# Exp_Board_Slolu.net
KiCad netlist of a schematic drawn in EAGLE
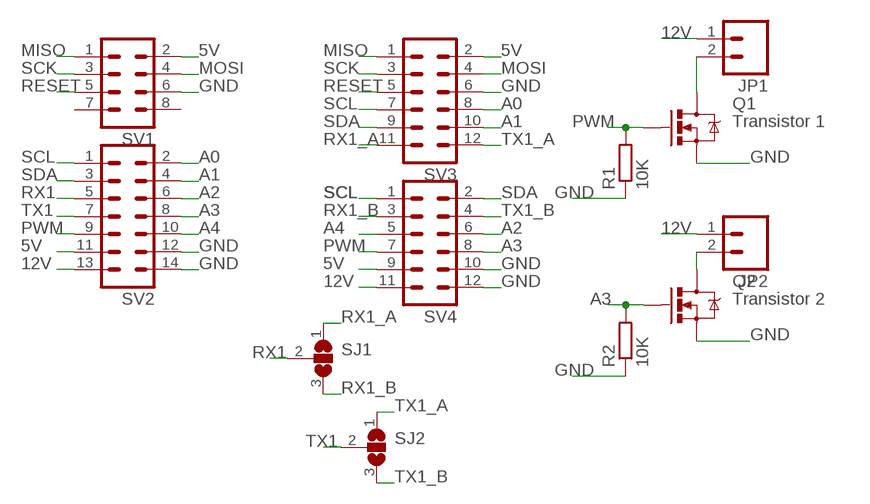
[diagram p0: schematic, sheet 1]

(export (version "E")
  (design (tool "Eeschema 10.0.6"))
  (components
    (comp (ref "JP1")
      (value "M02PTH")
      (footprint "eagle-import:1X02")
      (libsource (lib "eagle-import") (part "M02PTH"))
    )
    (comp (ref "JP2")
      (value "M02PTH")
      (footprint "eagle-import:1X02")
      (libsource (lib "eagle-import") (part "M02PTH"))
    )
    (comp (ref "Q1")
      (value "Transistor 1")
      (footprint "eagle-import:TO220V")
      (libsource (lib "eagle-import") (part "MOSFET-NCHANNELPTH2"))
    )
    (comp (ref "Q2")
      (value "Transistor 2")
      (footprint "eagle-import:TO220V")
      (libsource (lib "eagle-import") (part "MOSFET-NCHANNELPTH2"))
    )
    (comp (ref "R1")
      (value "10K")
      (footprint "eagle-import:0204_7")
      (libsource (lib "eagle-import") (part "R-EU_0204/7"))
    )
    (comp (ref "R2")
      (value "10K")
      (footprint "eagle-import:0204_7")
      (libsource (lib "eagle-import") (part "R-EU_0204/7"))
    )
    (comp (ref "SJ1")
      (value "SJ2W")
      (footprint "eagle-import:SJ_2")
      (libsource (lib "eagle-import") (part "SJ2W"))
    )
    (comp (ref "SJ2")
      (value "SJ2W")
      (footprint "eagle-import:SJ_2")
      (libsource (lib "eagle-import") (part "SJ2W"))
    )
    (comp (ref "SV1")
      (value "MA04-2")
      (footprint "eagle-import:MA04-2")
      (libsource (lib "eagle-import") (part "MA04-2"))
    )
    (comp (ref "SV2")
      (value "MA07-2")
      (footprint "eagle-import:MA07-2")
      (libsource (lib "eagle-import") (part "MA07-2"))
    )
    (comp (ref "SV3")
      (value "MA06-2")
      (footprint "eagle-import:MA06-2")
      (libsource (lib "eagle-import") (part "MA06-2"))
    )
    (comp (ref "SV4")
      (value "MA06-2")
      (footprint "eagle-import:MA06-2")
      (libsource (lib "eagle-import") (part "MA06-2"))
    )
  )
  (nets
    (net (code "1") (name "/5V") (class "Default")
      (node (ref "SV1") (pin "2") (pinfunction "2_2") (pintype "passive"))
      (node (ref "SV2") (pin "11") (pinfunction "11_11") (pintype "passive"))
      (node (ref "SV3") (pin "2") (pinfunction "2_2") (pintype "passive"))
      (node (ref "SV4") (pin "9") (pinfunction "9_9") (pintype "passive"))
    )
    (net (code "2") (name "/12V") (class "Default")
      (node (ref "JP1") (pin "1") (pinfunction "1_1") (pintype "passive"))
      (node (ref "JP2") (pin "1") (pinfunction "1_1") (pintype "passive"))
      (node (ref "SV2") (pin "13") (pinfunction "13_13") (pintype "passive"))
      (node (ref "SV4") (pin "11") (pinfunction "11_11") (pintype "passive"))
    )
    (net (code "3") (name "/A0") (class "Default")
      (node (ref "SV2") (pin "2") (pinfunction "2_2") (pintype "passive"))
      (node (ref "SV3") (pin "8") (pinfunction "8_8") (pintype "passive"))
    )
    (net (code "4") (name "/A1") (class "Default")
      (node (ref "SV2") (pin "4") (pinfunction "4_4") (pintype "passive"))
      (node (ref "SV3") (pin "10") (pinfunction "10_10") (pintype "passive"))
    )
    (net (code "5") (name "/A2") (class "Default")
      (node (ref "SV2") (pin "6") (pinfunction "6_6") (pintype "passive"))
      (node (ref "SV4") (pin "6") (pinfunction "6_6") (pintype "passive"))
    )
    (net (code "6") (name "/A3") (class "Default")
      (node (ref "Q2") (pin "1") (pinfunction "G_1") (pintype "passive"))
      (node (ref "R2") (pin "2") (pinfunction "2_2") (pintype "passive"))
      (node (ref "SV2") (pin "8") (pinfunction "8_8") (pintype "passive"))
      (node (ref "SV4") (pin "8") (pinfunction "8_8") (pintype "passive"))
    )
    (net (code "7") (name "/A4") (class "Default")
      (node (ref "SV2") (pin "10") (pinfunction "10_10") (pintype "passive"))
      (node (ref "SV4") (pin "5") (pinfunction "5_5") (pintype "passive"))
    )
    (net (code "8") (name "/GND") (class "Default")
      (node (ref "Q1") (pin "3") (pinfunction "S_3") (pintype "passive"))
      (node (ref "Q2") (pin "3") (pinfunction "S_3") (pintype "passive"))
      (node (ref "R1") (pin "1") (pinfunction "1_1") (pintype "passive"))
      (node (ref "R2") (pin "1") (pinfunction "1_1") (pintype "passive"))
      (node (ref "SV1") (pin "6") (pinfunction "6_6") (pintype "passive"))
      (node (ref "SV2") (pin "12") (pinfunction "12_12") (pintype "passive"))
      (node (ref "SV2") (pin "14") (pinfunction "14_14") (pintype "passive"))
      (node (ref "SV3") (pin "6") (pinfunction "6_6") (pintype "passive"))
      (node (ref "SV4") (pin "10") (pinfunction "10_10") (pintype "passive"))
      (node (ref "SV4") (pin "12") (pinfunction "12_12") (pintype "passive"))
    )
    (net (code "9") (name "/MISO") (class "Default")
      (node (ref "SV1") (pin "1") (pinfunction "1_1") (pintype "passive"))
      (node (ref "SV3") (pin "1") (pinfunction "1_1") (pintype "passive"))
    )
    (net (code "10") (name "/MOSI") (class "Default")
      (node (ref "SV1") (pin "4") (pinfunction "4_4") (pintype "passive"))
      (node (ref "SV3") (pin "4") (pinfunction "4_4") (pintype "passive"))
    )
    (net (code "11") (name "/PWM") (class "Default")
      (node (ref "Q1") (pin "1") (pinfunction "G_1") (pintype "passive"))
      (node (ref "R1") (pin "2") (pinfunction "2_2") (pintype "passive"))
      (node (ref "SV2") (pin "9") (pinfunction "9_9") (pintype "passive"))
      (node (ref "SV4") (pin "7") (pinfunction "7_7") (pintype "passive"))
    )
    (net (code "12") (name "/RESET") (class "Default")
      (node (ref "SV1") (pin "5") (pinfunction "5_5") (pintype "passive"))
      (node (ref "SV3") (pin "5") (pinfunction "5_5") (pintype "passive"))
    )
    (net (code "13") (name "/RX1") (class "Default")
      (node (ref "SJ1") (pin "2") (pinfunction "2_2") (pintype "passive"))
      (node (ref "SV2") (pin "5") (pinfunction "5_5") (pintype "passive"))
    )
    (net (code "14") (name "/RX1_A") (class "Default")
      (node (ref "SJ1") (pin "1") (pinfunction "1_1") (pintype "passive"))
      (node (ref "SV3") (pin "11") (pinfunction "11_11") (pintype "passive"))
    )
    (net (code "15") (name "/RX1_B") (class "Default")
      (node (ref "SJ1") (pin "3") (pinfunction "3_3") (pintype "passive"))
      (node (ref "SV4") (pin "3") (pinfunction "3_3") (pintype "passive"))
    )
    (net (code "16") (name "/SCK") (class "Default")
      (node (ref "SV1") (pin "3") (pinfunction "3_3") (pintype "passive"))
      (node (ref "SV3") (pin "3") (pinfunction "3_3") (pintype "passive"))
    )
    (net (code "17") (name "/SCL") (class "Default")
      (node (ref "SV2") (pin "1") (pinfunction "1_1") (pintype "passive"))
      (node (ref "SV3") (pin "7") (pinfunction "7_7") (pintype "passive"))
      (node (ref "SV4") (pin "1") (pinfunction "1_1") (pintype "passive"))
    )
    (net (code "18") (name "/SDA") (class "Default")
      (node (ref "SV2") (pin "3") (pinfunction "3_3") (pintype "passive"))
      (node (ref "SV3") (pin "9") (pinfunction "9_9") (pintype "passive"))
      (node (ref "SV4") (pin "2") (pinfunction "2_2") (pintype "passive"))
    )
    (net (code "19") (name "/TX1") (class "Default")
      (node (ref "SJ2") (pin "2") (pinfunction "2_2") (pintype "passive"))
      (node (ref "SV2") (pin "7") (pinfunction "7_7") (pintype "passive"))
    )
    (net (code "20") (name "/TX1_A") (class "Default")
      (node (ref "SJ2") (pin "1") (pinfunction "1_1") (pintype "passive"))
      (node (ref "SV3") (pin "12") (pinfunction "12_12") (pintype "passive"))
    )
    (net (code "21") (name "/TX1_B") (class "Default")
      (node (ref "SJ2") (pin "3") (pinfunction "3_3") (pintype "passive"))
      (node (ref "SV4") (pin "4") (pinfunction "4_4") (pintype "passive"))
    )
    (net (code "22") (name "Net-(Q1-D)") (class "Default")
      (node (ref "JP1") (pin "2") (pinfunction "2_2") (pintype "passive"))
      (node (ref "Q1") (pin "2") (pinfunction "D_2") (pintype "passive"))
    )
    (net (code "23") (name "Net-(Q2-D)") (class "Default")
      (node (ref "JP2") (pin "2") (pinfunction "2_2") (pintype "passive"))
      (node (ref "Q2") (pin "2") (pinfunction "D_2") (pintype "passive"))
    )
    (net (code "24") (name "unconnected-(SV1-Pad7)") (class "Default")
      (node (ref "SV1") (pin "7") (pinfunction "7_7") (pintype "passive"))
    )
    (net (code "25") (name "unconnected-(SV1-Pad8)") (class "Default")
      (node (ref "SV1") (pin "8") (pinfunction "8_8") (pintype "passive"))
    )
  )
)
